# Filtro.net
KiCad netlist of a schematic drawn in Altium Designer
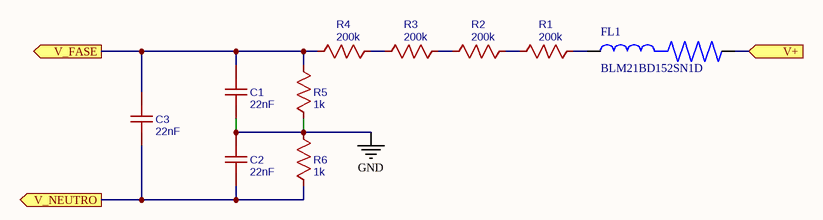
[diagram p0: Filtro.SchDoc]

(export (version "E")
  (design (tool "Eeschema 10.0.6"))
  (components
    (comp (ref "C1")
      (value "22nF")
      (footprint "GRM31C5C1E104GA01L:CAPC3216X190")
      (libsource (lib "altium-import") (part "root_0_22nF_"))
    )
    (comp (ref "C2")
      (value "22nF")
      (footprint "GRM31C5C1E104GA01L:CAPC3216X190")
      (libsource (lib "altium-import") (part "root_0_22nF_"))
    )
    (comp (ref "C3")
      (value "22nF")
      (footprint "GRM31C5C1E104GA01L:CAPC3216X190")
      (libsource (lib "altium-import") (part "root_0_22nF_"))
    )
    (comp (ref "FL1")
      (value "BLM21BD152SN1D")
      (footprint "BEADC2012X105N")
      (description "1.5 kOhms @ 100MHz 1 Signal Line Ferrite Bead 0805 (2012 Metric) 250mA 450mOhm")
      (fields (field (name "MF") "Murata"))
      (libsource (lib "BLM21BD152SN1D") (part "BLM21BD152SN1D"))
    )
    (comp (ref "R1")
      (value "200k")
      (footprint "SamacSys:RESC3216X75N")
      (libsource (lib "altium-import") (part "root_0_330k_"))
    )
    (comp (ref "R2")
      (value "200k")
      (footprint "SamacSys:RESC3216X75N")
      (libsource (lib "altium-import") (part "root_0_330k_"))
    )
    (comp (ref "R3")
      (value "200k")
      (footprint "SamacSys:RESC3216X75N")
      (libsource (lib "altium-import") (part "root_0_330k_"))
    )
    (comp (ref "R4")
      (value "200k")
      (footprint "SamacSys:RESC3216X75N")
      (libsource (lib "altium-import") (part "root_0_330k_"))
    )
    (comp (ref "R5")
      (value "1k")
      (footprint "SamacSys:RESC3216X75N")
      (libsource (lib "altium-import") (part "root_1_1k_"))
    )
    (comp (ref "R6")
      (value "1k")
      (footprint "SamacSys:RESC3216X75N")
      (libsource (lib "altium-import") (part "root_1_1k_"))
    )
  )
  (nets
    (net (code "1") (name "/V+") (class "Default")
      (node (ref "FL1") (pin "2") (pinfunction "2_2") (pintype "passive"))
    )
    (net (code "2") (name "/V_FASE") (class "Default")
      (node (ref "C1") (pin "2") (pinfunction "2_2") (pintype "passive"))
      (node (ref "C3") (pin "2") (pinfunction "2_2") (pintype "passive"))
      (node (ref "R4") (pin "1") (pinfunction "1_1") (pintype "passive"))
      (node (ref "R5") (pin "2") (pinfunction "2_2") (pintype "passive"))
    )
    (net (code "3") (name "/V_NEUTRO") (class "Default")
      (node (ref "C2") (pin "1") (pinfunction "1_1") (pintype "passive"))
      (node (ref "C3") (pin "1") (pinfunction "1_1") (pintype "passive"))
      (node (ref "R6") (pin "1") (pinfunction "1_1") (pintype "passive"))
    )
    (net (code "4") (name "GND") (class "Default")
      (node (ref "C1") (pin "1") (pinfunction "1_1") (pintype "passive"))
      (node (ref "C2") (pin "2") (pinfunction "2_2") (pintype "passive"))
      (node (ref "R5") (pin "1") (pinfunction "1_1") (pintype "passive"))
      (node (ref "R6") (pin "2") (pinfunction "2_2") (pintype "passive"))
    )
    (net (code "5") (name "Net-(FL1-Pad1)") (class "Default")
      (node (ref "FL1") (pin "1") (pinfunction "1_1") (pintype "passive"))
      (node (ref "R1") (pin "2") (pinfunction "2_2") (pintype "passive"))
    )
    (net (code "6") (name "Net-(R1-Pad1)") (class "Default")
      (node (ref "R1") (pin "1") (pinfunction "1_1") (pintype "passive"))
      (node (ref "R2") (pin "2") (pinfunction "2_2") (pintype "passive"))
    )
    (net (code "7") (name "Net-(R2-Pad1)") (class "Default")
      (node (ref "R2") (pin "1") (pinfunction "1_1") (pintype "passive"))
      (node (ref "R3") (pin "2") (pinfunction "2_2") (pintype "passive"))
    )
    (net (code "8") (name "Net-(R3-Pad1)") (class "Default")
      (node (ref "R3") (pin "1") (pinfunction "1_1") (pintype "passive"))
      (node (ref "R4") (pin "2") (pinfunction "2_2") (pintype "passive"))
    )
  )
)
